# bacchus.net
KiCad netlist of a schematic drawn in EAGLE
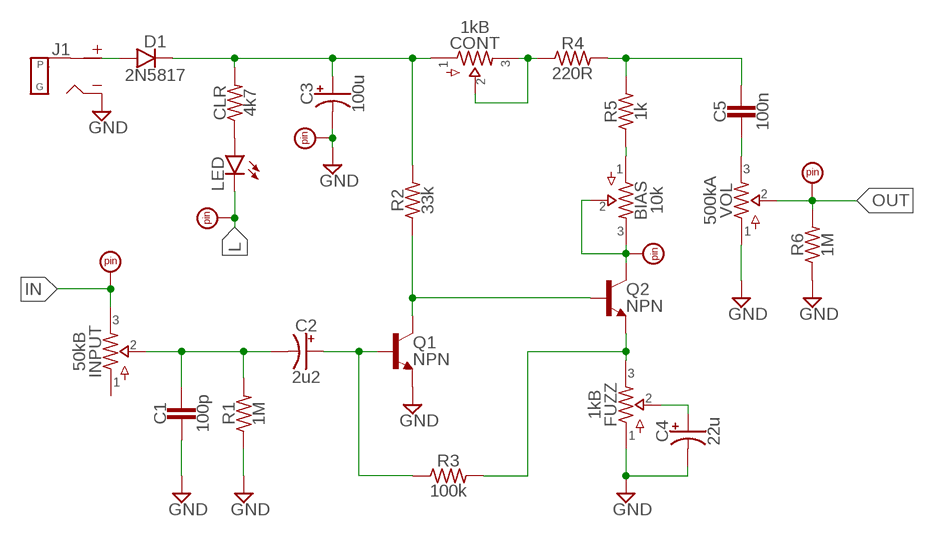
[diagram p0: schematic, sheet 1]

(export (version "E")
  (design (tool "Eeschema 10.0.6"))
  (components
    (comp (ref "BIAS")
      (value "10k")
      (footprint "eagle-import:2262_TRIM")
      (libsource (lib "eagle-import") (part "POTSTRIM"))
    )
    (comp (ref "C1")
      (value "100p")
      (footprint "eagle-import:050X030_025_2")
      (libsource (lib "eagle-import") (part "CER/FILM2"))
    )
    (comp (ref "C2")
      (value "2u2")
      (footprint "eagle-import:050_020_1")
      (libsource (lib "eagle-import") (part "0501"))
    )
    (comp (ref "C3")
      (value "100u")
      (footprint "eagle-import:050_020_1")
      (libsource (lib "eagle-import") (part "0501"))
    )
    (comp (ref "C4")
      (value "22u")
      (footprint "eagle-import:050_020_1")
      (libsource (lib "eagle-import") (part "0501"))
    )
    (comp (ref "C5")
      (value "100n")
      (footprint "eagle-import:050X030_025_2")
      (libsource (lib "eagle-import") (part "CER/FILM2"))
    )
    (comp (ref "CLR")
      (value "4k7")
      (footprint "eagle-import:R0207_3")
      (libsource (lib "eagle-import") (part "R_.3B"))
    )
    (comp (ref "CONT")
      (value "1kB")
      (footprint "eagle-import:9MM_W_MOUNTS")
      (libsource (lib "eagle-import") (part "POTS9MM_MOUNTED"))
    )
    (comp (ref "D1")
      (value "2N5817")
      (footprint "eagle-import:DO41-3")
      (libsource (lib "eagle-import") (part "DO41.3"))
    )
    (comp (ref "FUZZ")
      (value "1kB")
      (footprint "eagle-import:9MM_W_MOUNTS")
      (libsource (lib "eagle-import") (part "POTS9MM_MOUNTED"))
    )
    (comp (ref "GND")
      (value "PADRND")
      (footprint "eagle-import:ROUND")
      (libsource (lib "eagle-import") (part "PADRND"))
    )
    (comp (ref "IN")
      (value "PADSQR")
      (footprint "eagle-import:SQUARE")
      (libsource (lib "eagle-import") (part "PADSQR"))
    )
    (comp (ref "INPUT")
      (value "50kB")
      (footprint "eagle-import:9MM_W_MOUNTS")
      (libsource (lib "eagle-import") (part "POTS9MM_MOUNTED"))
    )
    (comp (ref "J1")
      (value "DC_MONO")
      (footprint "eagle-import:DC")
      (libsource (lib "eagle-import") (part "DC_MONO"))
    )
    (comp (ref "L")
      (value "PADRND")
      (footprint "eagle-import:ROUND")
      (libsource (lib "eagle-import") (part "PADRND"))
    )
    (comp (ref "LED")
      (value "LEDB")
      (footprint "eagle-import:3MM_B")
      (libsource (lib "eagle-import") (part "LEDB"))
    )
    (comp (ref "OUT")
      (value "PADSQR")
      (footprint "eagle-import:SQUARE")
      (libsource (lib "eagle-import") (part "PADSQR"))
    )
    (comp (ref "Q1")
      (value "NPN")
      (footprint "eagle-import:TO5")
      (libsource (lib "eagle-import") (part "2N1306"))
    )
    (comp (ref "Q2")
      (value "NPN")
      (footprint "eagle-import:TO5")
      (libsource (lib "eagle-import") (part "2N1306"))
    )
    (comp (ref "R1")
      (value "1M")
      (footprint "eagle-import:R0207_3")
      (libsource (lib "eagle-import") (part "R_.3B"))
    )
    (comp (ref "R2")
      (value "33k")
      (footprint "eagle-import:R0207_3")
      (libsource (lib "eagle-import") (part "R_.3B"))
    )
    (comp (ref "R3")
      (value "100k")
      (footprint "eagle-import:R0207_3")
      (libsource (lib "eagle-import") (part "R_.3B"))
    )
    (comp (ref "R4")
      (value "220R")
      (footprint "eagle-import:R0207_3")
      (libsource (lib "eagle-import") (part "R_.3B"))
    )
    (comp (ref "R5")
      (value "1k")
      (footprint "eagle-import:R0207_3")
      (libsource (lib "eagle-import") (part "R_.3B"))
    )
    (comp (ref "R6")
      (value "1M")
      (footprint "eagle-import:R0207_3")
      (libsource (lib "eagle-import") (part "R_.3B"))
    )
    (comp (ref "TP")
      (value "PADSQR")
      (footprint "eagle-import:SQUARE")
      (libsource (lib "eagle-import") (part "PADSQR"))
    )
    (comp (ref "VOL")
      (value "500kA")
      (footprint "eagle-import:9MM_W_MOUNTS")
      (libsource (lib "eagle-import") (part "POTS9MM_MOUNTED"))
    )
  )
  (nets
    (net (code "1") (name "GND") (class "Default")
      (node (ref "C1") (pin "2") (pinfunction "2_2") (pintype "passive"))
      (node (ref "C3") (pin "-") (pinfunction "-_-") (pintype "passive"))
      (node (ref "C4") (pin "-") (pinfunction "-_-") (pintype "passive"))
      (node (ref "FUZZ") (pin "P$1") (pinfunction "1_P$1") (pintype "passive"))
      (node (ref "GND") (pin "1") (pinfunction "P$1_1") (pintype "bidirectional"))
      (node (ref "J1") (pin "S") (pinfunction "SLEEVE_S") (pintype "passive"))
      (node (ref "Q1") (pin "1") (pinfunction "E_1") (pintype "passive"))
      (node (ref "R1") (pin "1") (pinfunction "1_1") (pintype "passive"))
      (node (ref "R6") (pin "1") (pinfunction "1_1") (pintype "passive"))
      (node (ref "VOL") (pin "P$1") (pinfunction "1_P$1") (pintype "passive"))
    )
    (net (code "2") (name "IN") (class "Default")
      (node (ref "IN") (pin "1") (pinfunction "P$1_1") (pintype "bidirectional"))
      (node (ref "INPUT") (pin "P$3") (pinfunction "3_P$3") (pintype "passive"))
    )
    (net (code "3") (name "L") (class "Default")
      (node (ref "L") (pin "1") (pinfunction "P$1_1") (pintype "bidirectional"))
      (node (ref "LED") (pin "K") (pinfunction "C_K") (pintype "passive"))
    )
    (net (code "4") (name "Net-(BIAS-Pad1)") (class "Default")
      (node (ref "BIAS") (pin "1") (pinfunction "1_1") (pintype "passive"))
      (node (ref "R5") (pin "1") (pinfunction "1_1") (pintype "passive"))
    )
    (net (code "5") (name "Net-(C5-Pad1)") (class "Default")
      (node (ref "C5") (pin "1") (pinfunction "1_1") (pintype "passive"))
      (node (ref "R4") (pin "2") (pinfunction "2_2") (pintype "passive"))
      (node (ref "R5") (pin "2") (pinfunction "2_2") (pintype "passive"))
    )
    (net (code "6") (name "Net-(CLR-Pad1)") (class "Default")
      (node (ref "CLR") (pin "1") (pinfunction "1_1") (pintype "passive"))
      (node (ref "LED") (pin "A") (pinfunction "A_A") (pintype "passive"))
    )
    (net (code "7") (name "Net-(CONT-1)") (class "Default")
      (node (ref "C3") (pin "+") (pinfunction "+_+") (pintype "passive"))
      (node (ref "CLR") (pin "2") (pinfunction "2_2") (pintype "passive"))
      (node (ref "CONT") (pin "P$1") (pinfunction "1_P$1") (pintype "passive"))
      (node (ref "D1") (pin "C") (pinfunction "C_C") (pintype "passive"))
      (node (ref "R2") (pin "2") (pinfunction "2_2") (pintype "passive"))
    )
    (net (code "8") (name "Net-(CONT-2)") (class "Default")
      (node (ref "CONT") (pin "P$2") (pinfunction "2_P$2") (pintype "passive"))
      (node (ref "CONT") (pin "P$3") (pinfunction "3_P$3") (pintype "passive"))
      (node (ref "R4") (pin "1") (pinfunction "1_1") (pintype "passive"))
    )
    (net (code "9") (name "Net-(FUZZ-2)") (class "Default")
      (node (ref "C4") (pin "+") (pinfunction "+_+") (pintype "passive"))
      (node (ref "FUZZ") (pin "P$2") (pinfunction "2_P$2") (pintype "passive"))
    )
    (net (code "10") (name "Net-(FUZZ-3)") (class "Default")
      (node (ref "FUZZ") (pin "P$3") (pinfunction "3_P$3") (pintype "passive"))
      (node (ref "Q2") (pin "1") (pinfunction "E_1") (pintype "passive"))
      (node (ref "R3") (pin "2") (pinfunction "2_2") (pintype "passive"))
    )
    (net (code "11") (name "Net-(INPUT-2)") (class "Default")
      (node (ref "C1") (pin "1") (pinfunction "1_1") (pintype "passive"))
      (node (ref "C2") (pin "-") (pinfunction "-_-") (pintype "passive"))
      (node (ref "INPUT") (pin "P$2") (pinfunction "2_P$2") (pintype "passive"))
      (node (ref "R1") (pin "2") (pinfunction "2_2") (pintype "passive"))
    )
    (net (code "12") (name "Net-(J1-TIP)") (class "Default")
      (node (ref "D1") (pin "A") (pinfunction "A_A") (pintype "passive"))
      (node (ref "J1") (pin "T") (pinfunction "TIP_T") (pintype "passive"))
    )
    (net (code "13") (name "Net-(Q1-B)") (class "Default")
      (node (ref "C2") (pin "+") (pinfunction "+_+") (pintype "passive"))
      (node (ref "Q1") (pin "2") (pinfunction "B_2") (pintype "passive"))
      (node (ref "R3") (pin "1") (pinfunction "1_1") (pintype "passive"))
    )
    (net (code "14") (name "Net-(Q1-C)") (class "Default")
      (node (ref "Q1") (pin "3") (pinfunction "C_3") (pintype "passive"))
      (node (ref "Q2") (pin "2") (pinfunction "B_2") (pintype "passive"))
      (node (ref "R2") (pin "1") (pinfunction "1_1") (pintype "passive"))
    )
    (net (code "15") (name "Net-(Q2-C)") (class "Default")
      (node (ref "BIAS") (pin "2") (pinfunction "2_2") (pintype "passive"))
      (node (ref "BIAS") (pin "3") (pinfunction "3_3") (pintype "passive"))
      (node (ref "Q2") (pin "3") (pinfunction "C_3") (pintype "passive"))
      (node (ref "TP") (pin "1") (pinfunction "P$1_1") (pintype "bidirectional"))
    )
    (net (code "16") (name "Net-(VOL-3)") (class "Default")
      (node (ref "C5") (pin "2") (pinfunction "2_2") (pintype "passive"))
      (node (ref "VOL") (pin "P$3") (pinfunction "3_P$3") (pintype "passive"))
    )
    (net (code "17") (name "OUT") (class "Default")
      (node (ref "OUT") (pin "1") (pinfunction "P$1_1") (pintype "bidirectional"))
      (node (ref "R6") (pin "2") (pinfunction "2_2") (pintype "passive"))
      (node (ref "VOL") (pin "P$2") (pinfunction "2_P$2") (pintype "passive"))
    )
    (net (code "18") (name "unconnected-(INPUT-1-PadP$1)") (class "Default")
      (node (ref "INPUT") (pin "P$1") (pinfunction "1_P$1") (pintype "passive"))
    )
  )
)
